# circuit.net
KiCad netlist of a schematic drawn in EAGLE
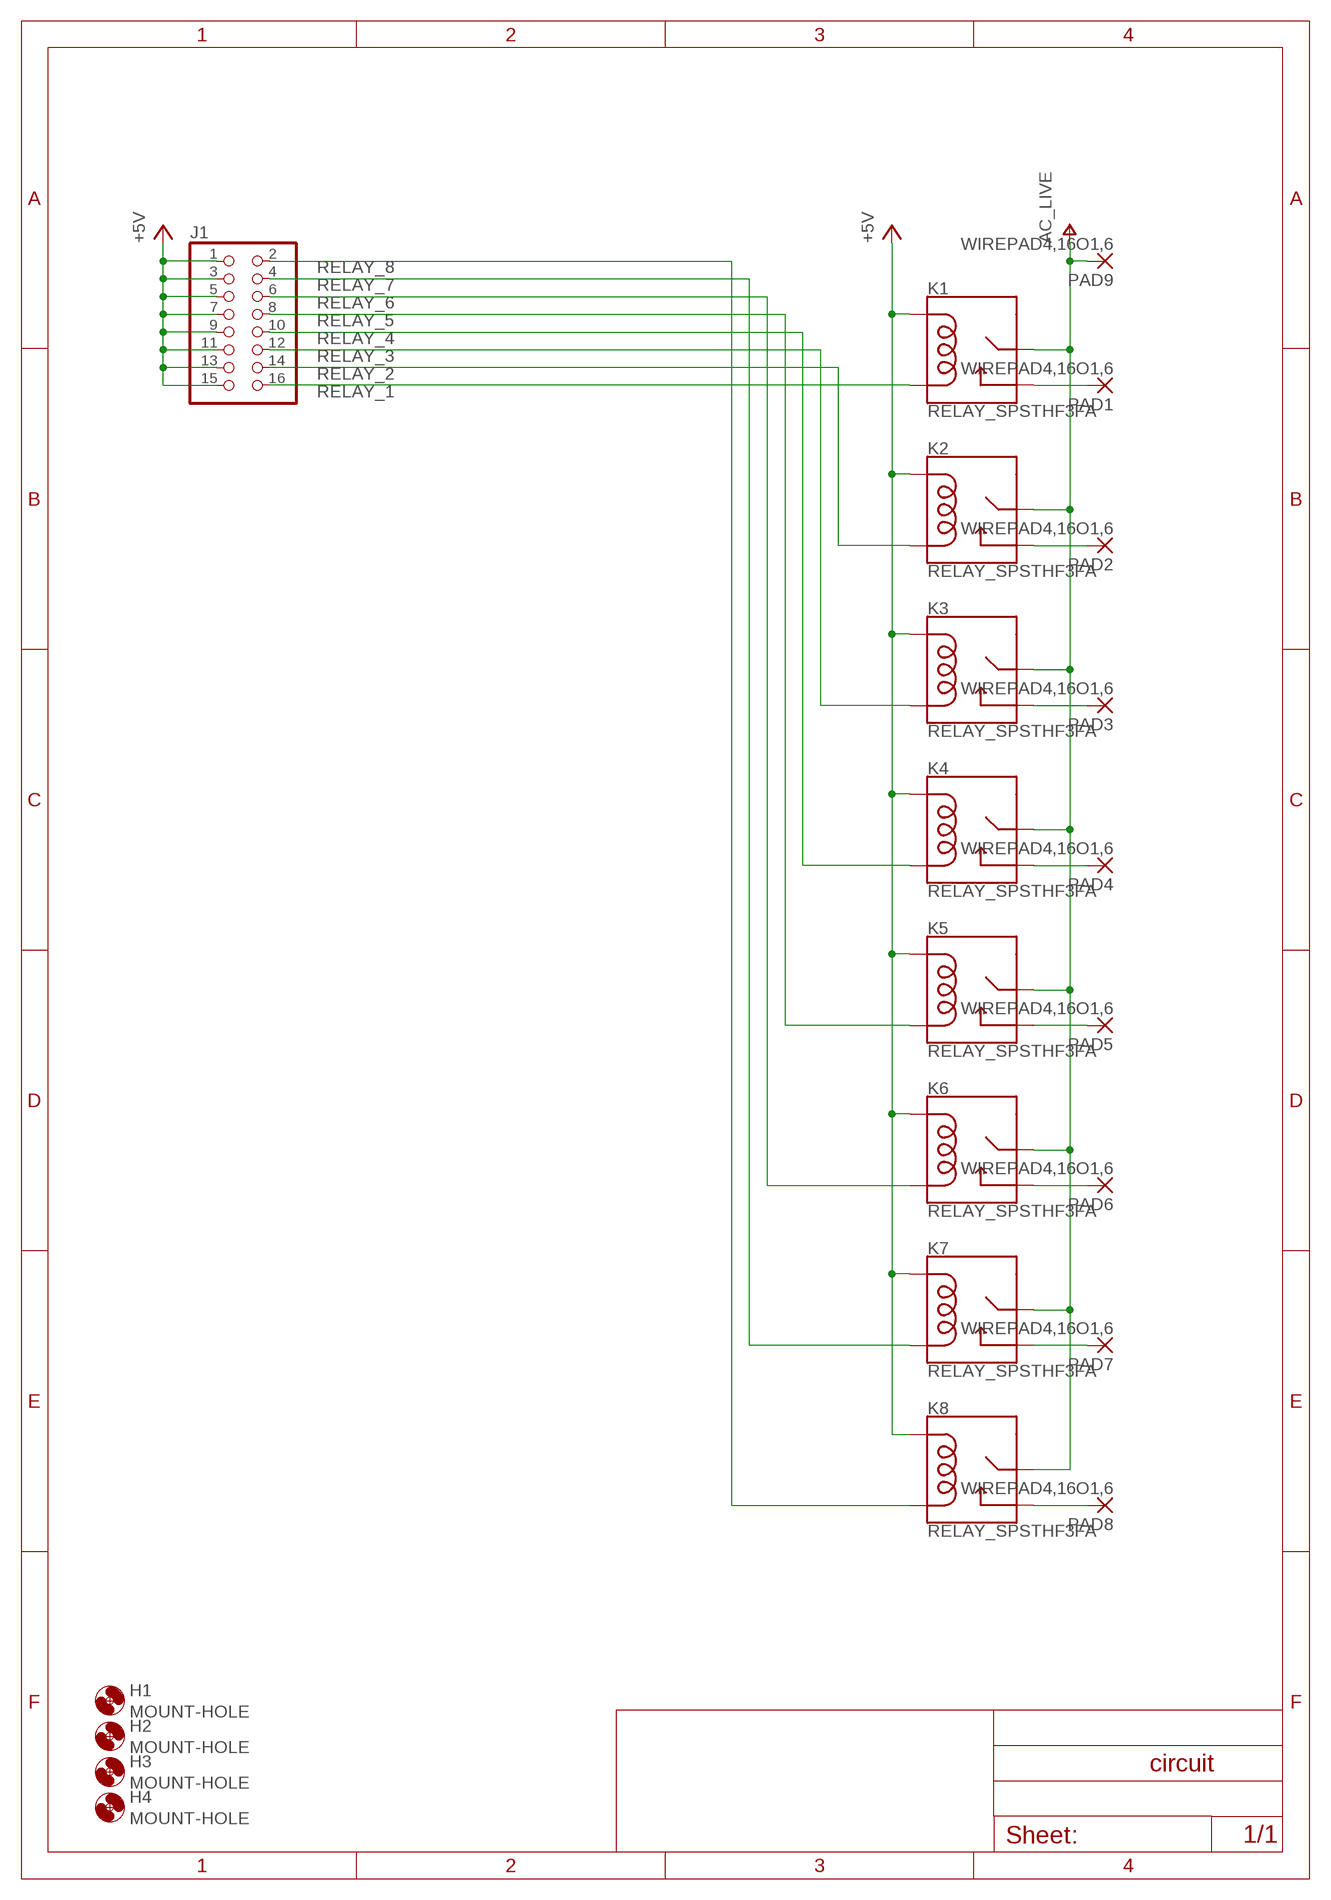
[diagram p0: schematic, sheet 1]

(export (version "E")
  (design (tool "Eeschema 10.0.6"))
  (components
    (comp (ref "H1")
      (value "MOUNT-HOLE")
      (footprint "eagle-import:3,2")
      (libsource (lib "eagle-import") (part "MOUNT-HOLE"))
    )
    (comp (ref "H2")
      (value "MOUNT-HOLE")
      (footprint "eagle-import:3,2")
      (libsource (lib "eagle-import") (part "MOUNT-HOLE"))
    )
    (comp (ref "H3")
      (value "MOUNT-HOLE")
      (footprint "eagle-import:3,2")
      (libsource (lib "eagle-import") (part "MOUNT-HOLE"))
    )
    (comp (ref "H4")
      (value "MOUNT-HOLE")
      (footprint "eagle-import:3,2")
      (libsource (lib "eagle-import") (part "MOUNT-HOLE"))
    )
    (comp (ref "J1")
      (value "LED")
      (footprint "eagle-import:2X08")
      (libsource (lib "eagle-import") (part "PINHD-2X8"))
    )
    (comp (ref "K1")
      (value "RELAY_SPSTHF3FA")
      (footprint "eagle-import:RELAY_HF3FA")
      (libsource (lib "eagle-import") (part "RELAY_SPSTHF3FA"))
    )
    (comp (ref "K2")
      (value "RELAY_SPSTHF3FA")
      (footprint "eagle-import:RELAY_HF3FA")
      (libsource (lib "eagle-import") (part "RELAY_SPSTHF3FA"))
    )
    (comp (ref "K3")
      (value "RELAY_SPSTHF3FA")
      (footprint "eagle-import:RELAY_HF3FA")
      (libsource (lib "eagle-import") (part "RELAY_SPSTHF3FA"))
    )
    (comp (ref "K4")
      (value "RELAY_SPSTHF3FA")
      (footprint "eagle-import:RELAY_HF3FA")
      (libsource (lib "eagle-import") (part "RELAY_SPSTHF3FA"))
    )
    (comp (ref "K5")
      (value "RELAY_SPSTHF3FA")
      (footprint "eagle-import:RELAY_HF3FA")
      (libsource (lib "eagle-import") (part "RELAY_SPSTHF3FA"))
    )
    (comp (ref "K6")
      (value "RELAY_SPSTHF3FA")
      (footprint "eagle-import:RELAY_HF3FA")
      (libsource (lib "eagle-import") (part "RELAY_SPSTHF3FA"))
    )
    (comp (ref "K7")
      (value "RELAY_SPSTHF3FA")
      (footprint "eagle-import:RELAY_HF3FA")
      (libsource (lib "eagle-import") (part "RELAY_SPSTHF3FA"))
    )
    (comp (ref "K8")
      (value "RELAY_SPSTHF3FA")
      (footprint "eagle-import:RELAY_HF3FA")
      (libsource (lib "eagle-import") (part "RELAY_SPSTHF3FA"))
    )
    (comp (ref "PAD1")
      (value "WIREPAD4,16O1,6")
      (footprint "eagle-import:4,16O1,6")
      (libsource (lib "eagle-import") (part "WIREPAD4,16O1,6"))
    )
    (comp (ref "PAD2")
      (value "WIREPAD4,16O1,6")
      (footprint "eagle-import:4,16O1,6")
      (libsource (lib "eagle-import") (part "WIREPAD4,16O1,6"))
    )
    (comp (ref "PAD3")
      (value "WIREPAD4,16O1,6")
      (footprint "eagle-import:4,16O1,6")
      (libsource (lib "eagle-import") (part "WIREPAD4,16O1,6"))
    )
    (comp (ref "PAD4")
      (value "WIREPAD4,16O1,6")
      (footprint "eagle-import:4,16O1,6")
      (libsource (lib "eagle-import") (part "WIREPAD4,16O1,6"))
    )
    (comp (ref "PAD5")
      (value "WIREPAD4,16O1,6")
      (footprint "eagle-import:4,16O1,6")
      (libsource (lib "eagle-import") (part "WIREPAD4,16O1,6"))
    )
    (comp (ref "PAD6")
      (value "WIREPAD4,16O1,6")
      (footprint "eagle-import:4,16O1,6")
      (libsource (lib "eagle-import") (part "WIREPAD4,16O1,6"))
    )
    (comp (ref "PAD7")
      (value "WIREPAD4,16O1,6")
      (footprint "eagle-import:4,16O1,6")
      (libsource (lib "eagle-import") (part "WIREPAD4,16O1,6"))
    )
    (comp (ref "PAD8")
      (value "WIREPAD4,16O1,6")
      (footprint "eagle-import:4,16O1,6")
      (libsource (lib "eagle-import") (part "WIREPAD4,16O1,6"))
    )
    (comp (ref "PAD9")
      (value "WIREPAD4,16O1,6")
      (footprint "eagle-import:4,16O1,6")
      (libsource (lib "eagle-import") (part "WIREPAD4,16O1,6"))
    )
  )
  (nets
    (net (code "1") (name "+5V") (class "Default")
      (node (ref "J1") (pin "1") (pinfunction "1_1") (pintype "passive"))
      (node (ref "J1") (pin "11") (pinfunction "11_11") (pintype "passive"))
      (node (ref "J1") (pin "13") (pinfunction "13_13") (pintype "passive"))
      (node (ref "J1") (pin "15") (pinfunction "15_15") (pintype "passive"))
      (node (ref "J1") (pin "3") (pinfunction "3_3") (pintype "passive"))
      (node (ref "J1") (pin "5") (pinfunction "5_5") (pintype "passive"))
      (node (ref "J1") (pin "7") (pinfunction "7_7") (pintype "passive"))
      (node (ref "J1") (pin "9") (pinfunction "9_9") (pintype "passive"))
      (node (ref "K1") (pin "P$1") (pinfunction "COIL1_P$1") (pintype "bidirectional"))
      (node (ref "K2") (pin "P$1") (pinfunction "COIL1_P$1") (pintype "bidirectional"))
      (node (ref "K3") (pin "P$1") (pinfunction "COIL1_P$1") (pintype "bidirectional"))
      (node (ref "K4") (pin "P$1") (pinfunction "COIL1_P$1") (pintype "bidirectional"))
      (node (ref "K5") (pin "P$1") (pinfunction "COIL1_P$1") (pintype "bidirectional"))
      (node (ref "K6") (pin "P$1") (pinfunction "COIL1_P$1") (pintype "bidirectional"))
      (node (ref "K7") (pin "P$1") (pinfunction "COIL1_P$1") (pintype "bidirectional"))
      (node (ref "K8") (pin "P$1") (pinfunction "COIL1_P$1") (pintype "bidirectional"))
    )
    (net (code "2") (name "/RELAY_1") (class "Default")
      (node (ref "J1") (pin "16") (pinfunction "16_16") (pintype "passive"))
      (node (ref "K1") (pin "P$2") (pinfunction "COIL2_P$2") (pintype "bidirectional"))
    )
    (net (code "3") (name "/RELAY_2") (class "Default")
      (node (ref "J1") (pin "14") (pinfunction "14_14") (pintype "passive"))
      (node (ref "K2") (pin "P$2") (pinfunction "COIL2_P$2") (pintype "bidirectional"))
    )
    (net (code "4") (name "/RELAY_3") (class "Default")
      (node (ref "J1") (pin "12") (pinfunction "12_12") (pintype "passive"))
      (node (ref "K3") (pin "P$2") (pinfunction "COIL2_P$2") (pintype "bidirectional"))
    )
    (net (code "5") (name "/RELAY_4") (class "Default")
      (node (ref "J1") (pin "10") (pinfunction "10_10") (pintype "passive"))
      (node (ref "K4") (pin "P$2") (pinfunction "COIL2_P$2") (pintype "bidirectional"))
    )
    (net (code "6") (name "/RELAY_5") (class "Default")
      (node (ref "J1") (pin "8") (pinfunction "8_8") (pintype "passive"))
      (node (ref "K5") (pin "P$2") (pinfunction "COIL2_P$2") (pintype "bidirectional"))
    )
    (net (code "7") (name "/RELAY_6") (class "Default")
      (node (ref "J1") (pin "6") (pinfunction "6_6") (pintype "passive"))
      (node (ref "K6") (pin "P$2") (pinfunction "COIL2_P$2") (pintype "bidirectional"))
    )
    (net (code "8") (name "/RELAY_7") (class "Default")
      (node (ref "J1") (pin "4") (pinfunction "4_4") (pintype "passive"))
      (node (ref "K7") (pin "P$2") (pinfunction "COIL2_P$2") (pintype "bidirectional"))
    )
    (net (code "9") (name "/RELAY_8") (class "Default")
      (node (ref "J1") (pin "2") (pinfunction "2_2") (pintype "passive"))
      (node (ref "K8") (pin "P$2") (pinfunction "COIL2_P$2") (pintype "bidirectional"))
    )
    (net (code "10") (name "AC_LIVE") (class "Default")
      (node (ref "K1") (pin "P$4") (pinfunction "MAIN_P$4") (pintype "bidirectional"))
      (node (ref "K2") (pin "P$4") (pinfunction "MAIN_P$4") (pintype "bidirectional"))
      (node (ref "K3") (pin "P$4") (pinfunction "MAIN_P$4") (pintype "bidirectional"))
      (node (ref "K4") (pin "P$4") (pinfunction "MAIN_P$4") (pintype "bidirectional"))
      (node (ref "K5") (pin "P$4") (pinfunction "MAIN_P$4") (pintype "bidirectional"))
      (node (ref "K6") (pin "P$4") (pinfunction "MAIN_P$4") (pintype "bidirectional"))
      (node (ref "K7") (pin "P$4") (pinfunction "MAIN_P$4") (pintype "bidirectional"))
      (node (ref "K8") (pin "P$4") (pinfunction "MAIN_P$4") (pintype "bidirectional"))
      (node (ref "PAD9") (pin "1") (pinfunction "P_1") (pintype "passive"))
    )
    (net (code "11") (name "Net-(K1-NO)") (class "Default")
      (node (ref "K1") (pin "P$3") (pinfunction "NO_P$3") (pintype "bidirectional"))
      (node (ref "PAD1") (pin "1") (pinfunction "P_1") (pintype "passive"))
    )
    (net (code "12") (name "Net-(K2-NO)") (class "Default")
      (node (ref "K2") (pin "P$3") (pinfunction "NO_P$3") (pintype "bidirectional"))
      (node (ref "PAD2") (pin "1") (pinfunction "P_1") (pintype "passive"))
    )
    (net (code "13") (name "Net-(K3-NO)") (class "Default")
      (node (ref "K3") (pin "P$3") (pinfunction "NO_P$3") (pintype "bidirectional"))
      (node (ref "PAD3") (pin "1") (pinfunction "P_1") (pintype "passive"))
    )
    (net (code "14") (name "Net-(K4-NO)") (class "Default")
      (node (ref "K4") (pin "P$3") (pinfunction "NO_P$3") (pintype "bidirectional"))
      (node (ref "PAD4") (pin "1") (pinfunction "P_1") (pintype "passive"))
    )
    (net (code "15") (name "Net-(K5-NO)") (class "Default")
      (node (ref "K5") (pin "P$3") (pinfunction "NO_P$3") (pintype "bidirectional"))
      (node (ref "PAD5") (pin "1") (pinfunction "P_1") (pintype "passive"))
    )
    (net (code "16") (name "Net-(K6-NO)") (class "Default")
      (node (ref "K6") (pin "P$3") (pinfunction "NO_P$3") (pintype "bidirectional"))
      (node (ref "PAD6") (pin "1") (pinfunction "P_1") (pintype "passive"))
    )
    (net (code "17") (name "Net-(K7-NO)") (class "Default")
      (node (ref "K7") (pin "P$3") (pinfunction "NO_P$3") (pintype "bidirectional"))
      (node (ref "PAD7") (pin "1") (pinfunction "P_1") (pintype "passive"))
    )
    (net (code "18") (name "Net-(K8-NO)") (class "Default")
      (node (ref "K8") (pin "P$3") (pinfunction "NO_P$3") (pintype "bidirectional"))
      (node (ref "PAD8") (pin "1") (pinfunction "P_1") (pintype "passive"))
    )
  )
)
